# QCopterFC_CAMSPI_Sch.net
KiCad netlist of a schematic drawn in Altium Designer
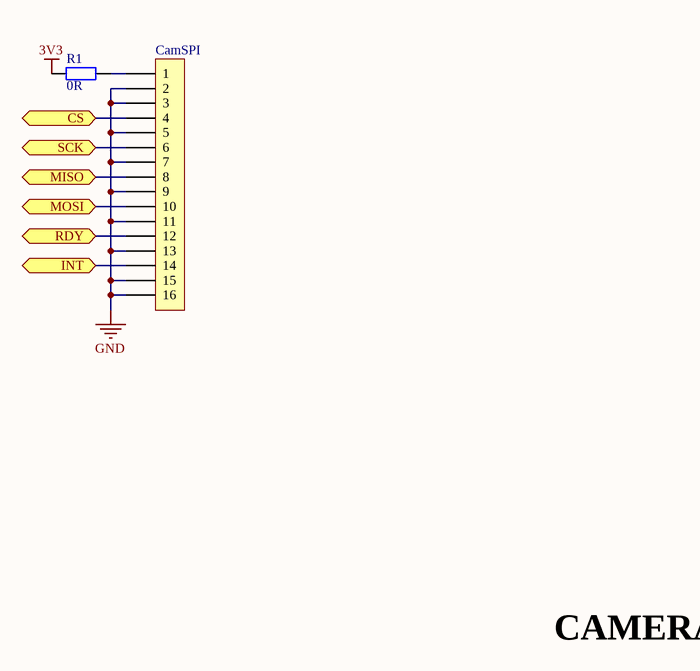
[diagram p0: QCopterFC_CAMSPI_Sch.SchDoc]

(export (version "E")
  (design (tool "Eeschema 10.0.6"))
  (components
    (comp (ref "CamSPI")
      (value "FFC_0.5_16")
      (footprint "PCB_Connector:FFC_0.5_16")
      (description "FFC")
      (libsource (lib "SCH_Connector") (part "FFC_0.5_16"))
    )
    (comp (ref "R1")
      (value "0R")
      (footprint "PCB_Passive:RES_0603")
      (description "Resistor")
      (fields (field (name "Comment") "Res_0603"))
      (libsource (lib "SCH_Passive") (part "Res_0603"))
    )
  )
  (nets
    (net (code "1") (name "/CS") (class "Default")
      (node (ref "CamSPI") (pin "4") (pinfunction "4_4") (pintype "passive"))
    )
    (net (code "2") (name "/INT") (class "Default")
      (node (ref "CamSPI") (pin "14") (pinfunction "14_14") (pintype "passive"))
    )
    (net (code "3") (name "/MISO") (class "Default")
      (node (ref "CamSPI") (pin "8") (pinfunction "8_8") (pintype "passive"))
    )
    (net (code "4") (name "/MOSI") (class "Default")
      (node (ref "CamSPI") (pin "10") (pinfunction "10_10") (pintype "passive"))
    )
    (net (code "5") (name "/RDY") (class "Default")
      (node (ref "CamSPI") (pin "12") (pinfunction "12_12") (pintype "passive"))
    )
    (net (code "6") (name "/SCK") (class "Default")
      (node (ref "CamSPI") (pin "6") (pinfunction "6_6") (pintype "passive"))
    )
    (net (code "7") (name "3V3") (class "Default")
      (node (ref "R1") (pin "1") (pinfunction "1_1") (pintype "passive"))
    )
    (net (code "8") (name "GND") (class "Default")
      (node (ref "CamSPI") (pin "11") (pinfunction "11_11") (pintype "passive"))
      (node (ref "CamSPI") (pin "13") (pinfunction "13_13") (pintype "passive"))
      (node (ref "CamSPI") (pin "15") (pinfunction "15_15") (pintype "passive"))
      (node (ref "CamSPI") (pin "16") (pinfunction "16_16") (pintype "passive"))
      (node (ref "CamSPI") (pin "2") (pinfunction "2_2") (pintype "passive"))
      (node (ref "CamSPI") (pin "3") (pinfunction "3_3") (pintype "passive"))
      (node (ref "CamSPI") (pin "5") (pinfunction "5_5") (pintype "passive"))
      (node (ref "CamSPI") (pin "7") (pinfunction "7_7") (pintype "passive"))
      (node (ref "CamSPI") (pin "9") (pinfunction "9_9") (pintype "passive"))
    )
    (net (code "9") (name "Net-(CamSPI-Pad1)") (class "Default")
      (node (ref "CamSPI") (pin "1") (pinfunction "1_1") (pintype "passive"))
      (node (ref "R1") (pin "2") (pinfunction "2_2") (pintype "passive"))
    )
  )
)
